# Right_bottom_4_leds.net
KiCad netlist of a schematic drawn in EAGLE
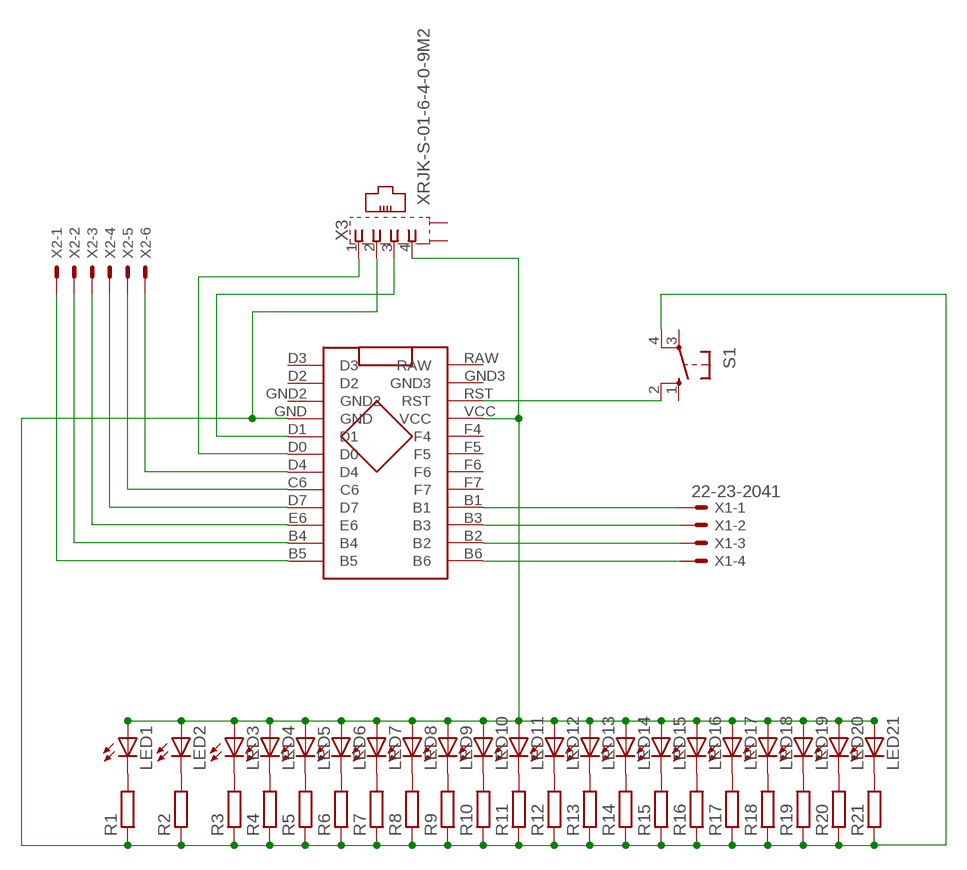
[diagram p0: schematic, sheet 1]

(export (version "E")
  (design (tool "Eeschema 10.0.6"))
  (components
    (comp (ref "LED1")
      (value "LED3MM")
      (footprint "eagle-import:LED3MM")
      (libsource (lib "eagle-import") (part "LED3MM"))
    )
    (comp (ref "LED2")
      (value "LED3MM")
      (footprint "eagle-import:LED3MM")
      (libsource (lib "eagle-import") (part "LED3MM"))
    )
    (comp (ref "LED3")
      (value "LED3MM")
      (footprint "eagle-import:LED3MM")
      (libsource (lib "eagle-import") (part "LED3MM"))
    )
    (comp (ref "LED4")
      (value "LED3MM")
      (footprint "eagle-import:LED3MM")
      (libsource (lib "eagle-import") (part "LED3MM"))
    )
    (comp (ref "LED5")
      (value "LED3MM")
      (footprint "eagle-import:LED3MM")
      (libsource (lib "eagle-import") (part "LED3MM"))
    )
    (comp (ref "LED6")
      (value "LED3MM")
      (footprint "eagle-import:LED3MM")
      (libsource (lib "eagle-import") (part "LED3MM"))
    )
    (comp (ref "LED7")
      (value "LED3MM")
      (footprint "eagle-import:LED3MM")
      (libsource (lib "eagle-import") (part "LED3MM"))
    )
    (comp (ref "LED8")
      (value "LED3MM")
      (footprint "eagle-import:LED3MM")
      (libsource (lib "eagle-import") (part "LED3MM"))
    )
    (comp (ref "LED9")
      (value "LED3MM")
      (footprint "eagle-import:LED3MM")
      (libsource (lib "eagle-import") (part "LED3MM"))
    )
    (comp (ref "LED10")
      (value "LED3MM")
      (footprint "eagle-import:LED3MM")
      (libsource (lib "eagle-import") (part "LED3MM"))
    )
    (comp (ref "LED11")
      (value "LED3MM")
      (footprint "eagle-import:LED3MM")
      (libsource (lib "eagle-import") (part "LED3MM"))
    )
    (comp (ref "LED12")
      (value "LED3MM")
      (footprint "eagle-import:LED3MM")
      (libsource (lib "eagle-import") (part "LED3MM"))
    )
    (comp (ref "LED13")
      (value "LED3MM")
      (footprint "eagle-import:LED3MM")
      (libsource (lib "eagle-import") (part "LED3MM"))
    )
    (comp (ref "LED14")
      (value "LED3MM")
      (footprint "eagle-import:LED3MM")
      (libsource (lib "eagle-import") (part "LED3MM"))
    )
    (comp (ref "LED15")
      (value "LED3MM")
      (footprint "eagle-import:LED3MM")
      (libsource (lib "eagle-import") (part "LED3MM"))
    )
    (comp (ref "LED16")
      (value "LED3MM")
      (footprint "eagle-import:LED3MM")
      (libsource (lib "eagle-import") (part "LED3MM"))
    )
    (comp (ref "LED17")
      (value "LED3MM")
      (footprint "eagle-import:LED3MM")
      (libsource (lib "eagle-import") (part "LED3MM"))
    )
    (comp (ref "LED18")
      (value "LED3MM")
      (footprint "eagle-import:LED3MM")
      (libsource (lib "eagle-import") (part "LED3MM"))
    )
    (comp (ref "LED19")
      (value "LED3MM")
      (footprint "eagle-import:LED3MM")
      (libsource (lib "eagle-import") (part "LED3MM"))
    )
    (comp (ref "LED20")
      (value "LED3MM")
      (footprint "eagle-import:LED3MM")
      (libsource (lib "eagle-import") (part "LED3MM"))
    )
    (comp (ref "LED21")
      (value "LED3MM")
      (footprint "eagle-import:LED3MM")
      (libsource (lib "eagle-import") (part "LED3MM"))
    )
    (comp (ref "R1")
      (value "R-EU_0204/7")
      (footprint "eagle-import:0204_7")
      (libsource (lib "eagle-import") (part "R-EU_0204/7"))
    )
    (comp (ref "R2")
      (value "R-EU_0204/7")
      (footprint "eagle-import:0204_7")
      (libsource (lib "eagle-import") (part "R-EU_0204/7"))
    )
    (comp (ref "R3")
      (value "R-EU_0204/7")
      (footprint "eagle-import:0204_7")
      (libsource (lib "eagle-import") (part "R-EU_0204/7"))
    )
    (comp (ref "R4")
      (value "R-EU_0204/7")
      (footprint "eagle-import:0204_7")
      (libsource (lib "eagle-import") (part "R-EU_0204/7"))
    )
    (comp (ref "R5")
      (value "R-EU_0204/7")
      (footprint "eagle-import:0204_7")
      (libsource (lib "eagle-import") (part "R-EU_0204/7"))
    )
    (comp (ref "R6")
      (value "R-EU_0204/7")
      (footprint "eagle-import:0204_7")
      (libsource (lib "eagle-import") (part "R-EU_0204/7"))
    )
    (comp (ref "R7")
      (value "R-EU_0204/7")
      (footprint "eagle-import:0204_7")
      (libsource (lib "eagle-import") (part "R-EU_0204/7"))
    )
    (comp (ref "R8")
      (value "R-EU_0204/7")
      (footprint "eagle-import:0204_7")
      (libsource (lib "eagle-import") (part "R-EU_0204/7"))
    )
    (comp (ref "R9")
      (value "R-EU_0204/7")
      (footprint "eagle-import:0204_7")
      (libsource (lib "eagle-import") (part "R-EU_0204/7"))
    )
    (comp (ref "R10")
      (value "R-EU_0204/7")
      (footprint "eagle-import:0204_7")
      (libsource (lib "eagle-import") (part "R-EU_0204/7"))
    )
    (comp (ref "R11")
      (value "R-EU_0204/7")
      (footprint "eagle-import:0204_7")
      (libsource (lib "eagle-import") (part "R-EU_0204/7"))
    )
    (comp (ref "R12")
      (value "R-EU_0204/7")
      (footprint "eagle-import:0204_7")
      (libsource (lib "eagle-import") (part "R-EU_0204/7"))
    )
    (comp (ref "R13")
      (value "R-EU_0204/7")
      (footprint "eagle-import:0204_7")
      (libsource (lib "eagle-import") (part "R-EU_0204/7"))
    )
    (comp (ref "R14")
      (value "R-EU_0204/7")
      (footprint "eagle-import:0204_7")
      (libsource (lib "eagle-import") (part "R-EU_0204/7"))
    )
    (comp (ref "R15")
      (value "R-EU_0204/7")
      (footprint "eagle-import:0204_7")
      (libsource (lib "eagle-import") (part "R-EU_0204/7"))
    )
    (comp (ref "R16")
      (value "R-EU_0204/7")
      (footprint "eagle-import:0204_7")
      (libsource (lib "eagle-import") (part "R-EU_0204/7"))
    )
    (comp (ref "R17")
      (value "R-EU_0204/7")
      (footprint "eagle-import:0204_7")
      (libsource (lib "eagle-import") (part "R-EU_0204/7"))
    )
    (comp (ref "R18")
      (value "R-EU_0204/7")
      (footprint "eagle-import:0204_7")
      (libsource (lib "eagle-import") (part "R-EU_0204/7"))
    )
    (comp (ref "R19")
      (value "R-EU_0204/7")
      (footprint "eagle-import:0204_7")
      (libsource (lib "eagle-import") (part "R-EU_0204/7"))
    )
    (comp (ref "R20")
      (value "R-EU_0204/7")
      (footprint "eagle-import:0204_7")
      (libsource (lib "eagle-import") (part "R-EU_0204/7"))
    )
    (comp (ref "R21")
      (value "R-EU_0204/7")
      (footprint "eagle-import:0204_7")
      (libsource (lib "eagle-import") (part "R-EU_0204/7"))
    )
    (comp (ref "S1")
      (value "10-XX")
      (footprint "eagle-import:B3F-10XX")
      (fields (field (name "MPN") "B3F-1000"))
      (libsource (lib "eagle-import") (part "10-XX"))
    )
    (comp (ref "U$1")
      (value "ARDUINO_PRO_MICRO_HECTOR")
      (footprint "eagle-import:ARDUINO_PRO_MICRO_HECTOR")
      (libsource (lib "eagle-import") (part "ARDUINO_PRO_MICRO_HECTOR"))
    )
    (comp (ref "X1")
      (value "22-23-2041")
      (footprint "eagle-import:22-23-2041")
      (fields (field (name "MF") "MOLEX"))
      (libsource (lib "eagle-import") (part "22-23-2041"))
    )
    (comp (ref "X2")
      (value "22-23-2061")
      (footprint "eagle-import:22-23-2061")
      (fields (field (name "MF") "MOLEX"))
      (libsource (lib "eagle-import") (part "22-23-2061"))
    )
    (comp (ref "X3")
      (value "XRJK-S-01-6-4-0-9M2")
      (footprint "eagle-import:XRJK-S-01-6-4-0-9M2")
      (libsource (lib "eagle-import") (part "XRJK4-0-9M2-S-01-6-"))
    )
  )
  (nets
    (net (code "1") (name "Net-(LED1-C)") (class "Default")
      (node (ref "LED1") (pin "K") (pinfunction "C_K") (pintype "passive"))
      (node (ref "R1") (pin "2") (pinfunction "2_2") (pintype "passive"))
    )
    (net (code "2") (name "Net-(LED1-PadA)") (class "Default")
      (node (ref "LED1") (pin "A") (pinfunction "A_A") (pintype "passive"))
      (node (ref "LED10") (pin "A") (pinfunction "A_A") (pintype "passive"))
      (node (ref "LED11") (pin "A") (pinfunction "A_A") (pintype "passive"))
      (node (ref "LED12") (pin "A") (pinfunction "A_A") (pintype "passive"))
      (node (ref "LED13") (pin "A") (pinfunction "A_A") (pintype "passive"))
      (node (ref "LED14") (pin "A") (pinfunction "A_A") (pintype "passive"))
      (node (ref "LED15") (pin "A") (pinfunction "A_A") (pintype "passive"))
      (node (ref "LED16") (pin "A") (pinfunction "A_A") (pintype "passive"))
      (node (ref "LED17") (pin "A") (pinfunction "A_A") (pintype "passive"))
      (node (ref "LED18") (pin "A") (pinfunction "A_A") (pintype "passive"))
      (node (ref "LED19") (pin "A") (pinfunction "A_A") (pintype "passive"))
      (node (ref "LED2") (pin "A") (pinfunction "A_A") (pintype "passive"))
      (node (ref "LED20") (pin "A") (pinfunction "A_A") (pintype "passive"))
      (node (ref "LED21") (pin "A") (pinfunction "A_A") (pintype "passive"))
      (node (ref "LED3") (pin "A") (pinfunction "A_A") (pintype "passive"))
      (node (ref "LED4") (pin "A") (pinfunction "A_A") (pintype "passive"))
      (node (ref "LED5") (pin "A") (pinfunction "A_A") (pintype "passive"))
      (node (ref "LED6") (pin "A") (pinfunction "A_A") (pintype "passive"))
      (node (ref "LED7") (pin "A") (pinfunction "A_A") (pintype "passive"))
      (node (ref "LED8") (pin "A") (pinfunction "A_A") (pintype "passive"))
      (node (ref "LED9") (pin "A") (pinfunction "A_A") (pintype "passive"))
      (node (ref "U$1") (pin "VCC") (pinfunction "VCC_VCC") (pintype "bidirectional"))
      (node (ref "X3") (pin "4") (pinfunction "4_4") (pintype "passive"))
    )
    (net (code "3") (name "Net-(LED2-C)") (class "Default")
      (node (ref "LED2") (pin "K") (pinfunction "C_K") (pintype "passive"))
      (node (ref "R2") (pin "2") (pinfunction "2_2") (pintype "passive"))
    )
    (net (code "4") (name "Net-(LED3-C)") (class "Default")
      (node (ref "LED3") (pin "K") (pinfunction "C_K") (pintype "passive"))
      (node (ref "R3") (pin "2") (pinfunction "2_2") (pintype "passive"))
    )
    (net (code "5") (name "Net-(LED4-C)") (class "Default")
      (node (ref "LED4") (pin "K") (pinfunction "C_K") (pintype "passive"))
      (node (ref "R4") (pin "2") (pinfunction "2_2") (pintype "passive"))
    )
    (net (code "6") (name "Net-(LED5-C)") (class "Default")
      (node (ref "LED5") (pin "K") (pinfunction "C_K") (pintype "passive"))
      (node (ref "R5") (pin "2") (pinfunction "2_2") (pintype "passive"))
    )
    (net (code "7") (name "Net-(LED6-C)") (class "Default")
      (node (ref "LED6") (pin "K") (pinfunction "C_K") (pintype "passive"))
      (node (ref "R6") (pin "2") (pinfunction "2_2") (pintype "passive"))
    )
    (net (code "8") (name "Net-(LED7-C)") (class "Default")
      (node (ref "LED7") (pin "K") (pinfunction "C_K") (pintype "passive"))
      (node (ref "R7") (pin "2") (pinfunction "2_2") (pintype "passive"))
    )
    (net (code "9") (name "Net-(LED8-C)") (class "Default")
      (node (ref "LED8") (pin "K") (pinfunction "C_K") (pintype "passive"))
      (node (ref "R8") (pin "2") (pinfunction "2_2") (pintype "passive"))
    )
    (net (code "10") (name "Net-(LED9-C)") (class "Default")
      (node (ref "LED9") (pin "K") (pinfunction "C_K") (pintype "passive"))
      (node (ref "R9") (pin "2") (pinfunction "2_2") (pintype "passive"))
    )
    (net (code "11") (name "Net-(LED10-C)") (class "Default")
      (node (ref "LED10") (pin "K") (pinfunction "C_K") (pintype "passive"))
      (node (ref "R10") (pin "2") (pinfunction "2_2") (pintype "passive"))
    )
    (net (code "12") (name "Net-(LED11-C)") (class "Default")
      (node (ref "LED11") (pin "K") (pinfunction "C_K") (pintype "passive"))
      (node (ref "R11") (pin "2") (pinfunction "2_2") (pintype "passive"))
    )
    (net (code "13") (name "Net-(LED12-C)") (class "Default")
      (node (ref "LED12") (pin "K") (pinfunction "C_K") (pintype "passive"))
      (node (ref "R12") (pin "2") (pinfunction "2_2") (pintype "passive"))
    )
    (net (code "14") (name "Net-(LED13-C)") (class "Default")
      (node (ref "LED13") (pin "K") (pinfunction "C_K") (pintype "passive"))
      (node (ref "R13") (pin "2") (pinfunction "2_2") (pintype "passive"))
    )
    (net (code "15") (name "Net-(LED14-C)") (class "Default")
      (node (ref "LED14") (pin "K") (pinfunction "C_K") (pintype "passive"))
      (node (ref "R14") (pin "2") (pinfunction "2_2") (pintype "passive"))
    )
    (net (code "16") (name "Net-(LED15-C)") (class "Default")
      (node (ref "LED15") (pin "K") (pinfunction "C_K") (pintype "passive"))
      (node (ref "R15") (pin "2") (pinfunction "2_2") (pintype "passive"))
    )
    (net (code "17") (name "Net-(LED16-C)") (class "Default")
      (node (ref "LED16") (pin "K") (pinfunction "C_K") (pintype "passive"))
      (node (ref "R16") (pin "2") (pinfunction "2_2") (pintype "passive"))
    )
    (net (code "18") (name "Net-(LED17-C)") (class "Default")
      (node (ref "LED17") (pin "K") (pinfunction "C_K") (pintype "passive"))
      (node (ref "R17") (pin "2") (pinfunction "2_2") (pintype "passive"))
    )
    (net (code "19") (name "Net-(LED18-C)") (class "Default")
      (node (ref "LED18") (pin "K") (pinfunction "C_K") (pintype "passive"))
      (node (ref "R18") (pin "2") (pinfunction "2_2") (pintype "passive"))
    )
    (net (code "20") (name "Net-(LED19-C)") (class "Default")
      (node (ref "LED19") (pin "K") (pinfunction "C_K") (pintype "passive"))
      (node (ref "R19") (pin "2") (pinfunction "2_2") (pintype "passive"))
    )
    (net (code "21") (name "Net-(LED20-C)") (class "Default")
      (node (ref "LED20") (pin "K") (pinfunction "C_K") (pintype "passive"))
      (node (ref "R20") (pin "2") (pinfunction "2_2") (pintype "passive"))
    )
    (net (code "22") (name "Net-(LED21-C)") (class "Default")
      (node (ref "LED21") (pin "K") (pinfunction "C_K") (pintype "passive"))
      (node (ref "R21") (pin "2") (pinfunction "2_2") (pintype "passive"))
    )
    (net (code "23") (name "Net-(S1-P1)") (class "Default")
      (node (ref "R1") (pin "1") (pinfunction "1_1") (pintype "passive"))
      (node (ref "R10") (pin "1") (pinfunction "1_1") (pintype "passive"))
      (node (ref "R11") (pin "1") (pinfunction "1_1") (pintype "passive"))
      (node (ref "R12") (pin "1") (pinfunction "1_1") (pintype "passive"))
      (node (ref "R13") (pin "1") (pinfunction "1_1") (pintype "passive"))
      (node (ref "R14") (pin "1") (pinfunction "1_1") (pintype "passive"))
      (node (ref "R15") (pin "1") (pinfunction "1_1") (pintype "passive"))
      (node (ref "R16") (pin "1") (pinfunction "1_1") (pintype "passive"))
      (node (ref "R17") (pin "1") (pinfunction "1_1") (pintype "passive"))
      (node (ref "R18") (pin "1") (pinfunction "1_1") (pintype "passive"))
      (node (ref "R19") (pin "1") (pinfunction "1_1") (pintype "passive"))
      (node (ref "R2") (pin "1") (pinfunction "1_1") (pintype "passive"))
      (node (ref "R20") (pin "1") (pinfunction "1_1") (pintype "passive"))
      (node (ref "R21") (pin "1") (pinfunction "1_1") (pintype "passive"))
      (node (ref "R3") (pin "1") (pinfunction "1_1") (pintype "passive"))
      (node (ref "R4") (pin "1") (pinfunction "1_1") (pintype "passive"))
      (node (ref "R5") (pin "1") (pinfunction "1_1") (pintype "passive"))
      (node (ref "R6") (pin "1") (pinfunction "1_1") (pintype "passive"))
      (node (ref "R7") (pin "1") (pinfunction "1_1") (pintype "passive"))
      (node (ref "R8") (pin "1") (pinfunction "1_1") (pintype "passive"))
      (node (ref "R9") (pin "1") (pinfunction "1_1") (pintype "passive"))
      (node (ref "S1") (pin "4") (pinfunction "P1_4") (pintype "passive"))
      (node (ref "U$1") (pin "GND") (pinfunction "GND_GND") (pintype "bidirectional"))
      (node (ref "X3") (pin "2") (pinfunction "2_2") (pintype "passive"))
    )
    (net (code "24") (name "Net-(S1-S1)") (class "Default")
      (node (ref "S1") (pin "2") (pinfunction "S1_2") (pintype "passive"))
      (node (ref "U$1") (pin "RST") (pinfunction "RST_RST") (pintype "bidirectional"))
    )
    (net (code "25") (name "Net-(U$1-PadD0)") (class "Default")
      (node (ref "U$1") (pin "D0") (pinfunction "D0_D0") (pintype "bidirectional"))
      (node (ref "X3") (pin "1") (pinfunction "1_1") (pintype "passive"))
    )
    (net (code "26") (name "Net-(U$1-PadD1)") (class "Default")
      (node (ref "U$1") (pin "D1") (pinfunction "D1_D1") (pintype "bidirectional"))
      (node (ref "X3") (pin "3") (pinfunction "3_3") (pintype "passive"))
    )
    (net (code "27") (name "Net-(X1A-S)") (class "Default")
      (node (ref "U$1") (pin "B1") (pinfunction "B1_B1") (pintype "bidirectional"))
      (node (ref "X1") (pin "1") (pinfunction "S_1") (pintype "passive"))
    )
    (net (code "28") (name "Net-(X1B-S)") (class "Default")
      (node (ref "U$1") (pin "B3") (pinfunction "B3_B3") (pintype "bidirectional"))
      (node (ref "X1") (pin "2") (pinfunction "S_2") (pintype "passive"))
    )
    (net (code "29") (name "Net-(X1C-S)") (class "Default")
      (node (ref "U$1") (pin "B2") (pinfunction "B2_B2") (pintype "bidirectional"))
      (node (ref "X1") (pin "3") (pinfunction "S_3") (pintype "passive"))
    )
    (net (code "30") (name "Net-(X1D-S)") (class "Default")
      (node (ref "U$1") (pin "B6") (pinfunction "B6_B6") (pintype "bidirectional"))
      (node (ref "X1") (pin "4") (pinfunction "S_4") (pintype "passive"))
    )
    (net (code "31") (name "Net-(X2A-S)") (class "Default")
      (node (ref "U$1") (pin "B5") (pinfunction "B5_B5") (pintype "bidirectional"))
      (node (ref "X2") (pin "1") (pinfunction "S_1") (pintype "passive"))
    )
    (net (code "32") (name "Net-(X2B-S)") (class "Default")
      (node (ref "U$1") (pin "B4") (pinfunction "B4_B4") (pintype "bidirectional"))
      (node (ref "X2") (pin "2") (pinfunction "S_2") (pintype "passive"))
    )
    (net (code "33") (name "Net-(X2C-S)") (class "Default")
      (node (ref "U$1") (pin "E6") (pinfunction "E6_E6") (pintype "bidirectional"))
      (node (ref "X2") (pin "3") (pinfunction "S_3") (pintype "passive"))
    )
    (net (code "34") (name "Net-(X2D-S)") (class "Default")
      (node (ref "U$1") (pin "D7") (pinfunction "D7_D7") (pintype "bidirectional"))
      (node (ref "X2") (pin "4") (pinfunction "S_4") (pintype "passive"))
    )
    (net (code "35") (name "Net-(X2E-S)") (class "Default")
      (node (ref "U$1") (pin "C6") (pinfunction "C6_C6") (pintype "bidirectional"))
      (node (ref "X2") (pin "5") (pinfunction "S_5") (pintype "passive"))
    )
    (net (code "36") (name "Net-(X2F-S)") (class "Default")
      (node (ref "U$1") (pin "D4") (pinfunction "D4_D4") (pintype "bidirectional"))
      (node (ref "X2") (pin "6") (pinfunction "S_6") (pintype "passive"))
    )
    (net (code "37") (name "unconnected-(S1-P-Pad3)") (class "Default")
      (node (ref "S1") (pin "3") (pinfunction "P_3") (pintype "passive"))
    )
    (net (code "38") (name "unconnected-(S1-S-Pad1)") (class "Default")
      (node (ref "S1") (pin "1") (pinfunction "S_1") (pintype "passive"))
    )
    (net (code "39") (name "unconnected-(U$1-PadD2)") (class "Default")
      (node (ref "U$1") (pin "D2") (pinfunction "D2_D2") (pintype "bidirectional"))
    )
    (net (code "40") (name "unconnected-(U$1-PadD3)") (class "Default")
      (node (ref "U$1") (pin "D3") (pinfunction "D3_D3") (pintype "bidirectional"))
    )
    (net (code "41") (name "unconnected-(U$1-PadF4)") (class "Default")
      (node (ref "U$1") (pin "F4") (pinfunction "F4_F4") (pintype "bidirectional"))
    )
    (net (code "42") (name "unconnected-(U$1-PadF5)") (class "Default")
      (node (ref "U$1") (pin "F5") (pinfunction "F5_F5") (pintype "bidirectional"))
    )
    (net (code "43") (name "unconnected-(U$1-PadF6)") (class "Default")
      (node (ref "U$1") (pin "F6") (pinfunction "F6_F6") (pintype "bidirectional"))
    )
    (net (code "44") (name "unconnected-(U$1-PadF7)") (class "Default")
      (node (ref "U$1") (pin "F7") (pinfunction "F7_F7") (pintype "bidirectional"))
    )
    (net (code "45") (name "unconnected-(U$1-PadGND2)") (class "Default")
      (node (ref "U$1") (pin "GND2") (pinfunction "GND2_GND2") (pintype "bidirectional"))
    )
    (net (code "46") (name "unconnected-(U$1-PadGND3)") (class "Default")
      (node (ref "U$1") (pin "GND3") (pinfunction "GND3_GND3") (pintype "bidirectional"))
    )
    (net (code "47") (name "unconnected-(U$1-PadRAW)") (class "Default")
      (node (ref "U$1") (pin "RAW") (pinfunction "RAW_RAW") (pintype "bidirectional"))
    )
    (net (code "48") (name "unconnected-(X3-S-PadS1)") (class "Default")
      (node (ref "X3") (pin "S1") (pinfunction "S_S1") (pintype "passive"))
    )
    (net (code "49") (name "unconnected-(X3-S-PadS2)") (class "Default")
      (node (ref "X3") (pin "S2") (pinfunction "S_S2") (pintype "passive"))
    )
  )
)
